# Teensy.net
KiCad netlist of a schematic drawn in Altium Designer
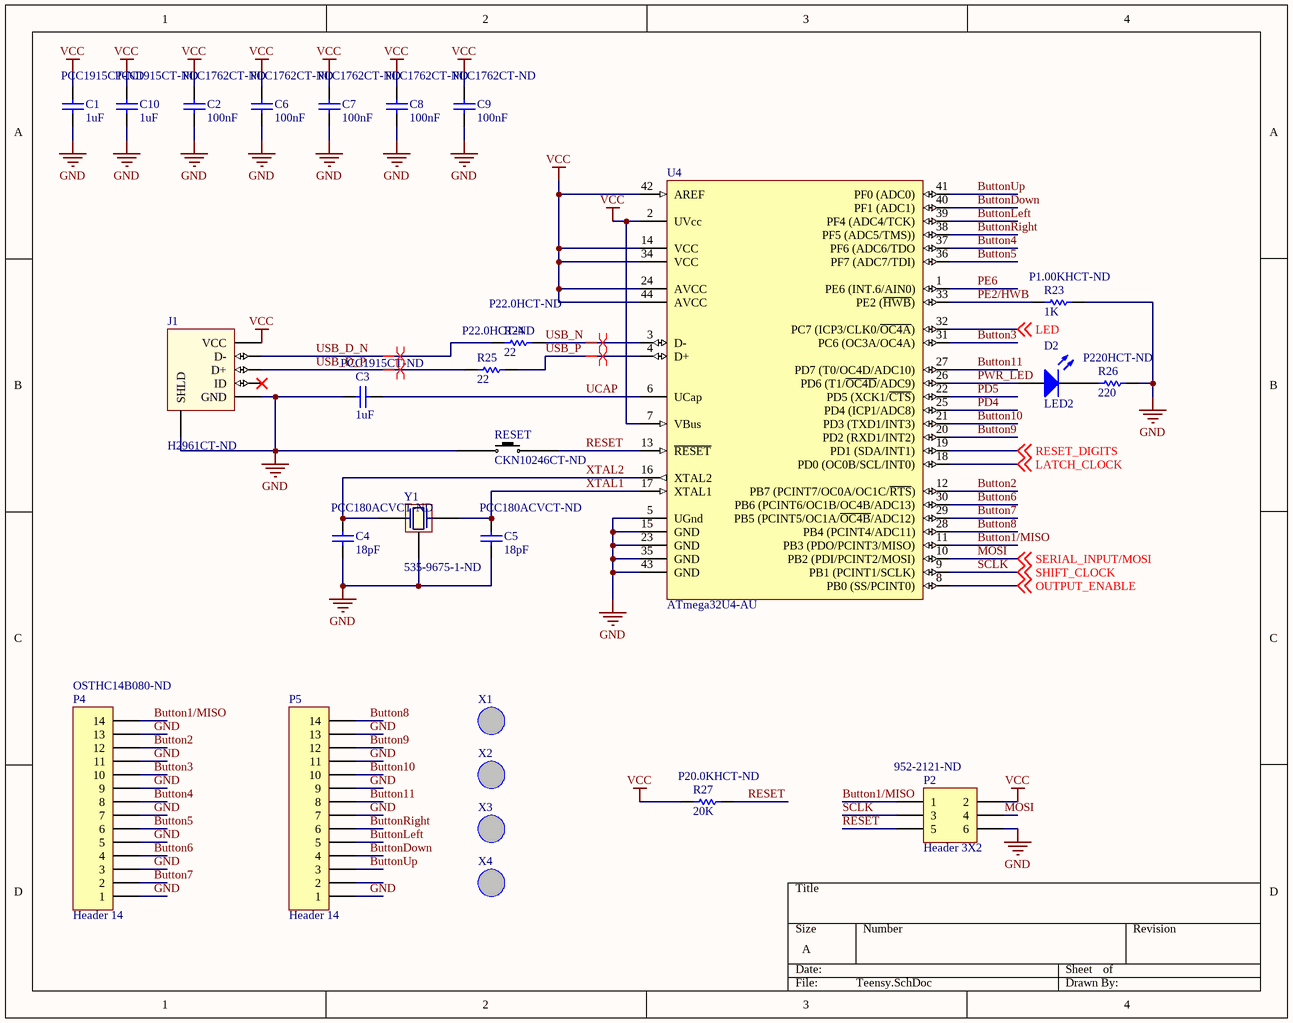
[diagram p0: Teensy.SchDoc]

(export (version "E")
  (design (tool "Eeschema 10.0.6"))
  (components
    (comp (ref "C1")
      (value "1uF")
      (footprint "1608[0603]")
      (description "Capacitor (Semiconductor SIM Model)")
      (fields
        (field (name "SUPPLIER PART NUMBER 1") "PCC1915CT-ND")
        (field (name "Comment") "Cap Semi")
        (field (name "PUBLISHER") "Altium Limited")
      )
      (libsource (lib "Miscellaneous Devices") (part "Cap Semi"))
    )
    (comp (ref "C2")
      (value "100nF")
      (footprint "1608[0603]")
      (description "Capacitor (Semiconductor SIM Model)")
      (fields
        (field (name "SUPPLIER PART NUMBER 1") "PCC1762CT-ND")
        (field (name "Comment") "Cap Semi")
        (field (name "PUBLISHER") "Altium Limited")
      )
      (libsource (lib "Miscellaneous Devices") (part "Cap Semi"))
    )
    (comp (ref "C3")
      (value "1uF")
      (footprint "1608[0603]")
      (description "Capacitor (Semiconductor SIM Model)")
      (fields
        (field (name "SUPPLIER PART NUMBER 1") "PCC1915CT-ND")
        (field (name "Comment") "Cap Semi")
        (field (name "PUBLISHER") "Altium Limited")
      )
      (libsource (lib "Miscellaneous Devices") (part "Cap Semi"))
    )
    (comp (ref "C4")
      (value "18pF")
      (footprint "1608[0603]")
      (description "Capacitor (Semiconductor SIM Model)")
      (fields
        (field (name "SUPPLIER PART NUMBER 1") "PCC180ACVCT-ND")
        (field (name "Comment") "Cap Semi")
        (field (name "PUBLISHER") "Altium Limited")
      )
      (libsource (lib "Miscellaneous Devices") (part "Cap Semi"))
    )
    (comp (ref "C5")
      (value "18pF")
      (footprint "1608[0603]")
      (description "Capacitor (Semiconductor SIM Model)")
      (fields
        (field (name "SUPPLIER PART NUMBER 1") "PCC180ACVCT-ND")
        (field (name "Comment") "Cap Semi")
        (field (name "PUBLISHER") "Altium Limited")
      )
      (libsource (lib "Miscellaneous Devices") (part "Cap Semi"))
    )
    (comp (ref "C6")
      (value "100nF")
      (footprint "1608[0603]")
      (description "Capacitor (Semiconductor SIM Model)")
      (fields
        (field (name "SUPPLIER PART NUMBER 1") "PCC1762CT-ND")
        (field (name "Comment") "Cap Semi")
        (field (name "PUBLISHER") "Altium Limited")
      )
      (libsource (lib "Miscellaneous Devices") (part "Cap Semi"))
    )
    (comp (ref "C7")
      (value "100nF")
      (footprint "1608[0603]")
      (description "Capacitor (Semiconductor SIM Model)")
      (fields
        (field (name "SUPPLIER PART NUMBER 1") "PCC1762CT-ND")
        (field (name "Comment") "Cap Semi")
        (field (name "PUBLISHER") "Altium Limited")
      )
      (libsource (lib "Miscellaneous Devices") (part "Cap Semi"))
    )
    (comp (ref "C8")
      (value "100nF")
      (footprint "1608[0603]")
      (description "Capacitor (Semiconductor SIM Model)")
      (fields
        (field (name "SUPPLIER PART NUMBER 1") "PCC1762CT-ND")
        (field (name "Comment") "Cap Semi")
        (field (name "PUBLISHER") "Altium Limited")
      )
      (libsource (lib "Miscellaneous Devices") (part "Cap Semi"))
    )
    (comp (ref "C9")
      (value "100nF")
      (footprint "1608[0603]")
      (description "Capacitor (Semiconductor SIM Model)")
      (fields
        (field (name "SUPPLIER PART NUMBER 1") "PCC1762CT-ND")
        (field (name "Comment") "Cap Semi")
        (field (name "PUBLISHER") "Altium Limited")
      )
      (libsource (lib "Miscellaneous Devices") (part "Cap Semi"))
    )
    (comp (ref "C10")
      (value "1uF")
      (footprint "1608[0603]")
      (description "Capacitor (Semiconductor SIM Model)")
      (fields
        (field (name "SUPPLIER PART NUMBER 1") "PCC1915CT-ND")
        (field (name "Comment") "Cap Semi")
        (field (name "PUBLISHER") "Altium Limited")
      )
      (libsource (lib "Miscellaneous Devices") (part "Cap Semi"))
    )
    (comp (ref "D2")
      (value "LED2")
      (footprint "INDC1608L")
      (description "475-2816-1-ND")
      (fields (field (name "PUBLISHER") "Altium Limited"))
      (libsource (lib "Miscellaneous Devices") (part "LED2"))
    )
    (comp (ref "J1")
      (value "UX60A-MB-5ST")
      (footprint "UX60A-MB-5ST")
      (description "USBMiniBSocket Metal Shield SMT Type Without Positioning Post")
      (fields (field (name "SUPPLIER PART NUMBER 1") "H2961CT-ND"))
      (libsource (lib "ArcadeJoystick") (part "UX60A-MB-5ST"))
    )
    (comp (ref "P2")
      (value "Header 3X2")
      (footprint "HDR2X3")
      (description "Header, 3-Pin, Dual row")
      (fields
        (field (name "SUPPLIER PART NUMBER 1") "952-2121-ND")
        (field (name "PUBLISHER") "Altium Limited")
      )
      (libsource (lib "Miscellaneous Connectors") (part "Header 3X2"))
    )
    (comp (ref "P4")
      (value "Header 14")
      (footprint "PTSA 0,5/14-2,5-Z")
      (description "Header, 14-Pin")
      (fields
        (field (name "SUPPLIER PART NUMBER 1") "OSTHC14B080-ND")
        (field (name "PUBLISHER") "Altium Limited")
      )
      (libsource (lib "Miscellaneous Connectors") (part "Header 14"))
    )
    (comp (ref "P5")
      (value "Header 14")
      (footprint "PTSA 0,5/14-2,5-Z")
      (description "Header, 14-Pin")
      (fields (field (name "PUBLISHER") "Altium Limited"))
      (libsource (lib "Miscellaneous Connectors") (part "Header 14"))
    )
    (comp (ref "R23")
      (value "1K")
      (footprint "1608[0603]")
      (description "Semiconductor Resistor")
      (fields
        (field (name "SUPPLIER PART NUMBER 1") "P1.00KHCT-ND")
        (field (name "Comment") "Res Semi")
        (field (name "PUBLISHER") "Altium Limited")
      )
      (libsource (lib "Miscellaneous Devices") (part "Res Semi"))
    )
    (comp (ref "R24")
      (value "22")
      (footprint "1608[0603]")
      (description "Semiconductor Resistor")
      (fields
        (field (name "SUPPLIER PART NUMBER 1") "P22.0HCT-ND")
        (field (name "Comment") "Res Semi")
        (field (name "PUBLISHER") "Altium Limited")
      )
      (libsource (lib "Miscellaneous Devices") (part "Res Semi"))
    )
    (comp (ref "R25")
      (value "22")
      (footprint "1608[0603]")
      (description "Semiconductor Resistor")
      (fields
        (field (name "SUPPLIER PART NUMBER 1") "P22.0HCT-ND")
        (field (name "Comment") "Res Semi")
        (field (name "PUBLISHER") "Altium Limited")
      )
      (libsource (lib "Miscellaneous Devices") (part "Res Semi"))
    )
    (comp (ref "R26")
      (value "220")
      (footprint "1608[0603]")
      (description "Semiconductor Resistor")
      (fields
        (field (name "SUPPLIER PART NUMBER 1") "P220HCT-ND")
        (field (name "Comment") "Res Semi")
        (field (name "PUBLISHER") "Altium Limited")
      )
      (libsource (lib "Miscellaneous Devices") (part "Res Semi"))
    )
    (comp (ref "R27")
      (value "20K")
      (footprint "1608[0603]")
      (description "Semiconductor Resistor")
      (fields
        (field (name "SUPPLIER PART NUMBER 1") "P20.0KHCT-ND")
        (field (name "Comment") "Res Semi")
        (field (name "PUBLISHER") "Altium Limited")
      )
      (libsource (lib "Miscellaneous Devices") (part "Res Semi"))
    )
    (comp (ref "RESET")
      (value "KMR231NGLFS")
      (footprint "KMR231NGLFS")
      (description "KMR 2 Series  Microminiature SMT Top Actuated")
      (fields (field (name "SUPPLIER PART NUMBER 1") "CKN10246CT-ND"))
      (libsource (lib "ArcadeJoystick") (part "KMR231NGLFS"))
    )
    (comp (ref "U4")
      (value "ATmega32U4-AU")
      (footprint "44ML_N")
      (fields (field (name "PUBLISHER") "Altium Limited"))
      (libsource (lib "Atmel Microcontroller 8-Bit megaAVR") (part "ATmega32U4-AU"))
    )
    (comp (ref "X1")
      (value "4-40 Hole")
      (footprint "4-40 Hole")
      (libsource (lib "ArcadeJoystick") (part "4-40 Hole"))
    )
    (comp (ref "X2")
      (value "4-40 Hole")
      (footprint "4-40 Hole")
      (libsource (lib "ArcadeJoystick") (part "4-40 Hole"))
    )
    (comp (ref "X3")
      (value "4-40 Hole")
      (footprint "4-40 Hole")
      (libsource (lib "ArcadeJoystick") (part "4-40 Hole"))
    )
    (comp (ref "X4")
      (value "4-40 Hole")
      (footprint "4-40 Hole")
      (libsource (lib "ArcadeJoystick") (part "4-40 Hole"))
    )
    (comp (ref "Y1")
      (value "ABM8-16.000MHZ-10-1-U-T")
      (footprint "ABM8-16.000MHZ-10-1-U-T")
      (description "Crystal Resonator")
      (fields (field (name "SUPPLIER PART NUMBER 1") "535-9675-1-ND"))
      (libsource (lib "ArcadeJoystick") (part "ABM8-16.000MHZ-10-1-U-T"))
    )
  )
  (nets
    (net (code "1") (name "/Button1{slash}MISO") (class "Default")
      (node (ref "P2") (pin "1") (pinfunction "1_1") (pintype "passive"))
      (node (ref "P4") (pin "14") (pinfunction "14_14") (pintype "passive"))
      (node (ref "U4") (pin "11") (pinfunction "PB3_(PDO/PCINT3/MISO)_11") (pintype "bidirectional"))
    )
    (net (code "2") (name "/Button2") (class "Default")
      (node (ref "P4") (pin "12") (pinfunction "12_12") (pintype "passive"))
      (node (ref "U4") (pin "12") (pinfunction "PB7_(PCINT7/OC0A/OC1C/~{RTS})_12") (pintype "bidirectional"))
    )
    (net (code "3") (name "/Button3") (class "Default")
      (node (ref "P4") (pin "10") (pinfunction "10_10") (pintype "passive"))
      (node (ref "U4") (pin "31") (pinfunction "PC6_(OC3A/OC4A)_31") (pintype "bidirectional"))
    )
    (net (code "4") (name "/Button4") (class "Default")
      (node (ref "P4") (pin "8") (pinfunction "8_8") (pintype "passive"))
      (node (ref "U4") (pin "37") (pinfunction "PF6_(ADC6/TDO_37") (pintype "bidirectional"))
    )
    (net (code "5") (name "/Button5") (class "Default")
      (node (ref "P4") (pin "6") (pinfunction "6_6") (pintype "passive"))
      (node (ref "U4") (pin "36") (pinfunction "PF7_(ADC7/TDI)_36") (pintype "bidirectional"))
    )
    (net (code "6") (name "/Button6") (class "Default")
      (node (ref "P4") (pin "4") (pinfunction "4_4") (pintype "passive"))
      (node (ref "U4") (pin "30") (pinfunction "PB6_(PCINT6/OC1B/OC4B/ADC13)_30") (pintype "bidirectional"))
    )
    (net (code "7") (name "/Button7") (class "Default")
      (node (ref "P4") (pin "2") (pinfunction "2_2") (pintype "passive"))
      (node (ref "U4") (pin "29") (pinfunction "PB5_(PCINT5/OC1A/~{OC4B}/ADC12)_29") (pintype "bidirectional"))
    )
    (net (code "8") (name "/Button8") (class "Default")
      (node (ref "P5") (pin "14") (pinfunction "14_14") (pintype "passive"))
      (node (ref "U4") (pin "28") (pinfunction "PB4_(PCINT4/ADC11)_28") (pintype "bidirectional"))
    )
    (net (code "9") (name "/Button9") (class "Default")
      (node (ref "P5") (pin "12") (pinfunction "12_12") (pintype "passive"))
      (node (ref "U4") (pin "20") (pinfunction "PD2_(RXD1/INT2)_20") (pintype "bidirectional"))
    )
    (net (code "10") (name "/Button10") (class "Default")
      (node (ref "P5") (pin "10") (pinfunction "10_10") (pintype "passive"))
      (node (ref "U4") (pin "21") (pinfunction "PD3_(TXD1/INT3)_21") (pintype "bidirectional"))
    )
    (net (code "11") (name "/Button11") (class "Default")
      (node (ref "P5") (pin "8") (pinfunction "8_8") (pintype "passive"))
      (node (ref "U4") (pin "27") (pinfunction "PD7_(T0/OC4D/ADC10)_27") (pintype "bidirectional"))
    )
    (net (code "12") (name "/ButtonDown") (class "Default")
      (node (ref "P5") (pin "4") (pinfunction "4_4") (pintype "passive"))
      (node (ref "U4") (pin "40") (pinfunction "PF1_(ADC1)_40") (pintype "bidirectional"))
    )
    (net (code "13") (name "/ButtonLeft") (class "Default")
      (node (ref "P5") (pin "5") (pinfunction "5_5") (pintype "passive"))
      (node (ref "U4") (pin "39") (pinfunction "PF4_(ADC4/TCK)_39") (pintype "bidirectional"))
    )
    (net (code "14") (name "/ButtonRight") (class "Default")
      (node (ref "P5") (pin "6") (pinfunction "6_6") (pintype "passive"))
      (node (ref "U4") (pin "38") (pinfunction "PF5_(ADC5/TMS))_38") (pintype "bidirectional"))
    )
    (net (code "15") (name "/ButtonUp") (class "Default")
      (node (ref "P5") (pin "3") (pinfunction "3_3") (pintype "passive"))
      (node (ref "U4") (pin "41") (pinfunction "PF0_(ADC0)_41") (pintype "bidirectional"))
    )
    (net (code "16") (name "/PD4") (class "Default")
      (node (ref "U4") (pin "25") (pinfunction "PD4_(ICP1/ADC8)_25") (pintype "bidirectional"))
    )
    (net (code "17") (name "/PD5") (class "Default")
      (node (ref "U4") (pin "22") (pinfunction "PD5_(XCK1/~{CTS})_22") (pintype "bidirectional"))
    )
    (net (code "18") (name "/PE2{slash}HWB") (class "Default")
      (node (ref "R23") (pin "1") (pinfunction "1_1") (pintype "passive"))
      (node (ref "U4") (pin "33") (pinfunction "PE2_(~{HWB})_33") (pintype "bidirectional"))
    )
    (net (code "19") (name "/PE6") (class "Default")
      (node (ref "U4") (pin "1") (pinfunction "PE6_(INT.6/AIN0)_1") (pintype "bidirectional"))
    )
    (net (code "20") (name "/PWR_LED") (class "Default")
      (node (ref "D2") (pin "1") (pinfunction "A_1") (pintype "passive"))
      (node (ref "U4") (pin "26") (pinfunction "PD6_(T1/~{OC4D}/ADC9)_26") (pintype "bidirectional"))
    )
    (net (code "21") (name "/RESET") (class "Default")
      (node (ref "P2") (pin "5") (pinfunction "5_5") (pintype "passive"))
      (node (ref "R27") (pin "2") (pinfunction "2_2") (pintype "passive"))
      (node (ref "RESET") (pin "2") (pintype "passive"))
      (node (ref "U4") (pin "13") (pinfunction "~{RESET}_13") (pintype "input"))
    )
    (net (code "22") (name "/UCAP") (class "Default")
      (node (ref "C3") (pin "1") (pinfunction "1_1") (pintype "passive"))
      (node (ref "U4") (pin "6") (pinfunction "UCap_6") (pintype "passive"))
    )
    (net (code "23") (name "/USB_D_N") (class "Default")
      (node (ref "J1") (pin "2") (pinfunction "D-_2") (pintype "bidirectional"))
      (node (ref "R24") (pin "1") (pinfunction "1_1") (pintype "passive"))
    )
    (net (code "24") (name "/USB_D_P") (class "Default")
      (node (ref "J1") (pin "3") (pinfunction "D+_3") (pintype "bidirectional"))
      (node (ref "R25") (pin "1") (pinfunction "1_1") (pintype "passive"))
    )
    (net (code "25") (name "/USB_N") (class "Default")
      (node (ref "R24") (pin "2") (pinfunction "2_2") (pintype "passive"))
      (node (ref "U4") (pin "3") (pinfunction "D-_3") (pintype "bidirectional"))
    )
    (net (code "26") (name "/USB_P") (class "Default")
      (node (ref "R25") (pin "2") (pinfunction "2_2") (pintype "passive"))
      (node (ref "U4") (pin "4") (pinfunction "D+_4") (pintype "bidirectional"))
    )
    (net (code "27") (name "/XTAL1") (class "Default")
      (node (ref "C5") (pin "2") (pinfunction "2_2") (pintype "passive"))
      (node (ref "U4") (pin "17") (pinfunction "XTAL1_17") (pintype "input"))
      (node (ref "Y1") (pin "4") (pintype "passive"))
    )
    (net (code "28") (name "/XTAL2") (class "Default")
      (node (ref "C4") (pin "2") (pinfunction "2_2") (pintype "passive"))
      (node (ref "U4") (pin "16") (pinfunction "XTAL2_16") (pintype "output"))
      (node (ref "Y1") (pin "2") (pintype "passive"))
    )
    (net (code "29") (name "GND") (class "Default")
      (node (ref "C1") (pin "1") (pinfunction "1_1") (pintype "passive"))
      (node (ref "C10") (pin "1") (pinfunction "1_1") (pintype "passive"))
      (node (ref "C2") (pin "2") (pinfunction "2_2") (pintype "passive"))
      (node (ref "C3") (pin "2") (pinfunction "2_2") (pintype "passive"))
      (node (ref "C4") (pin "1") (pinfunction "1_1") (pintype "passive"))
      (node (ref "C5") (pin "1") (pinfunction "1_1") (pintype "passive"))
      (node (ref "C6") (pin "2") (pinfunction "2_2") (pintype "passive"))
      (node (ref "C7") (pin "2") (pinfunction "2_2") (pintype "passive"))
      (node (ref "C8") (pin "2") (pinfunction "2_2") (pintype "passive"))
      (node (ref "C9") (pin "2") (pinfunction "2_2") (pintype "passive"))
      (node (ref "J1") (pin "0") (pinfunction "SHLD_0") (pintype "passive"))
      (node (ref "J1") (pin "5") (pinfunction "GND_5") (pintype "passive"))
      (node (ref "P2") (pin "6") (pinfunction "6_6") (pintype "passive"))
      (node (ref "P4") (pin "1") (pinfunction "1_1") (pintype "passive"))
      (node (ref "P4") (pin "11") (pinfunction "11_11") (pintype "passive"))
      (node (ref "P4") (pin "13") (pinfunction "13_13") (pintype "passive"))
      (node (ref "P4") (pin "3") (pinfunction "3_3") (pintype "passive"))
      (node (ref "P4") (pin "5") (pinfunction "5_5") (pintype "passive"))
      (node (ref "P4") (pin "7") (pinfunction "7_7") (pintype "passive"))
      (node (ref "P4") (pin "9") (pinfunction "9_9") (pintype "passive"))
      (node (ref "P5") (pin "1") (pinfunction "1_1") (pintype "passive"))
      (node (ref "P5") (pin "11") (pinfunction "11_11") (pintype "passive"))
      (node (ref "P5") (pin "13") (pinfunction "13_13") (pintype "passive"))
      (node (ref "P5") (pin "7") (pinfunction "7_7") (pintype "passive"))
      (node (ref "P5") (pin "9") (pinfunction "9_9") (pintype "passive"))
      (node (ref "R23") (pin "2") (pinfunction "2_2") (pintype "passive"))
      (node (ref "R26") (pin "1") (pinfunction "1_1") (pintype "passive"))
      (node (ref "RESET") (pin "1") (pintype "passive"))
      (node (ref "U4") (pin "15") (pinfunction "GND_15") (pintype "power_in"))
      (node (ref "U4") (pin "23") (pinfunction "GND_23") (pintype "power_in"))
      (node (ref "U4") (pin "35") (pinfunction "GND_35") (pintype "power_in"))
      (node (ref "U4") (pin "43") (pinfunction "GND_43") (pintype "power_in"))
      (node (ref "U4") (pin "5") (pinfunction "UGnd_5") (pintype "power_in"))
      (node (ref "Y1") (pin "0") (pinfunction "GND_0") (pintype "passive"))
    )
    (net (code "30") (name "LATCH_CLOCK") (class "Default")
      (node (ref "U4") (pin "18") (pinfunction "PD0_(OC0B/SCL/INT0)_18") (pintype "bidirectional"))
    )
    (net (code "31") (name "LED") (class "Default")
      (node (ref "U4") (pin "32") (pinfunction "PC7_(ICP3/CLK0/~{OC4A})_32") (pintype "bidirectional"))
    )
    (net (code "32") (name "Net-(D2-K)") (class "Default")
      (node (ref "D2") (pin "2") (pinfunction "K_2") (pintype "passive"))
      (node (ref "R26") (pin "2") (pinfunction "2_2") (pintype "passive"))
    )
    (net (code "33") (name "OUTPUT_ENABLE") (class "Default")
      (node (ref "U4") (pin "8") (pinfunction "PB0_(SS/PCINT0)_8") (pintype "bidirectional"))
    )
    (net (code "34") (name "RESET_DIGITS") (class "Default")
      (node (ref "U4") (pin "19") (pinfunction "PD1_(SDA/INT1)_19") (pintype "bidirectional"))
    )
    (net (code "35") (name "SERIAL_INPUT{slash}MOSI") (class "Default")
      (node (ref "P2") (pin "4") (pinfunction "4_4") (pintype "passive"))
      (node (ref "U4") (pin "10") (pinfunction "PB2_(PDI/PCINT2/MOSI)_10") (pintype "bidirectional"))
    )
    (net (code "36") (name "SHIFT_CLOCK") (class "Default")
      (node (ref "P2") (pin "3") (pinfunction "3_3") (pintype "passive"))
      (node (ref "U4") (pin "9") (pinfunction "PB1_(PCINT1/SCLK)_9") (pintype "bidirectional"))
    )
    (net (code "37") (name "VCC") (class "Default")
      (node (ref "C1") (pin "2") (pinfunction "2_2") (pintype "passive"))
      (node (ref "C10") (pin "2") (pinfunction "2_2") (pintype "passive"))
      (node (ref "C2") (pin "1") (pinfunction "1_1") (pintype "passive"))
      (node (ref "C6") (pin "1") (pinfunction "1_1") (pintype "passive"))
      (node (ref "C7") (pin "1") (pinfunction "1_1") (pintype "passive"))
      (node (ref "C8") (pin "1") (pinfunction "1_1") (pintype "passive"))
      (node (ref "C9") (pin "1") (pinfunction "1_1") (pintype "passive"))
      (node (ref "J1") (pin "1") (pinfunction "VCC_1") (pintype "power_in"))
      (node (ref "P2") (pin "2") (pinfunction "2_2") (pintype "passive"))
      (node (ref "R27") (pin "1") (pinfunction "1_1") (pintype "passive"))
      (node (ref "U4") (pin "14") (pinfunction "VCC_14") (pintype "power_in"))
      (node (ref "U4") (pin "2") (pinfunction "UVcc_2") (pintype "power_in"))
      (node (ref "U4") (pin "24") (pinfunction "AVCC_24") (pintype "power_in"))
      (node (ref "U4") (pin "34") (pinfunction "VCC_34") (pintype "power_in"))
      (node (ref "U4") (pin "42") (pinfunction "AREF_42") (pintype "input"))
      (node (ref "U4") (pin "44") (pinfunction "AVCC_44") (pintype "power_in"))
      (node (ref "U4") (pin "7") (pinfunction "VBus_7") (pintype "input"))
    )
    (net (code "38") (name "unconnected-(J1-ID-Pad4)") (class "Default")
      (node (ref "J1") (pin "4") (pinfunction "ID_4") (pintype "bidirectional+no_connect"))
    )
    (net (code "39") (name "unconnected-(P5-Pad2)") (class "Default")
      (node (ref "P5") (pin "2") (pinfunction "2_2") (pintype "passive"))
    )
  )
)
